# fite-controller-1-main.net
KiCad netlist of a schematic drawn in EAGLE
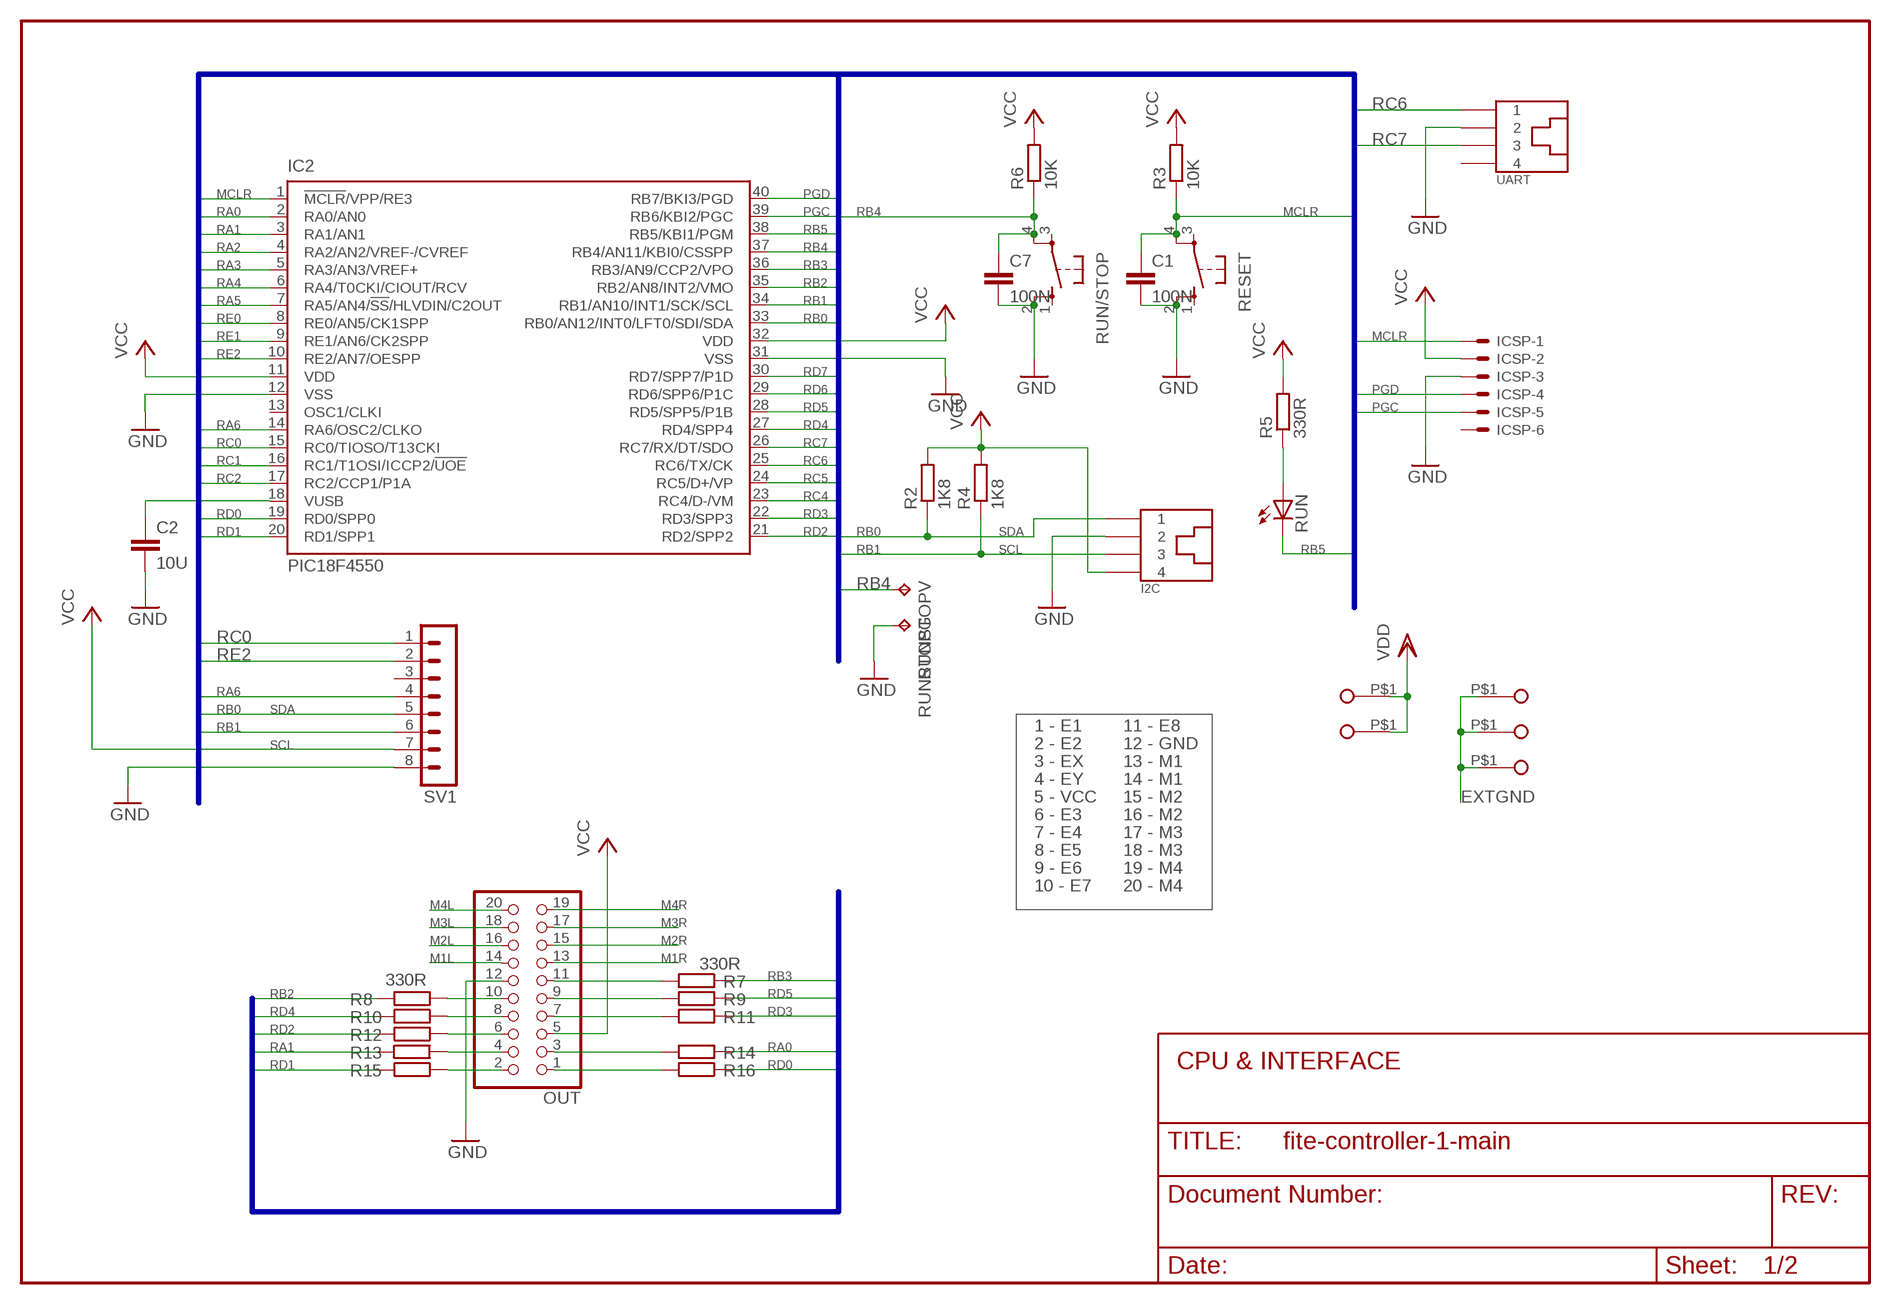
[diagram p0: schematic, sheet 1]
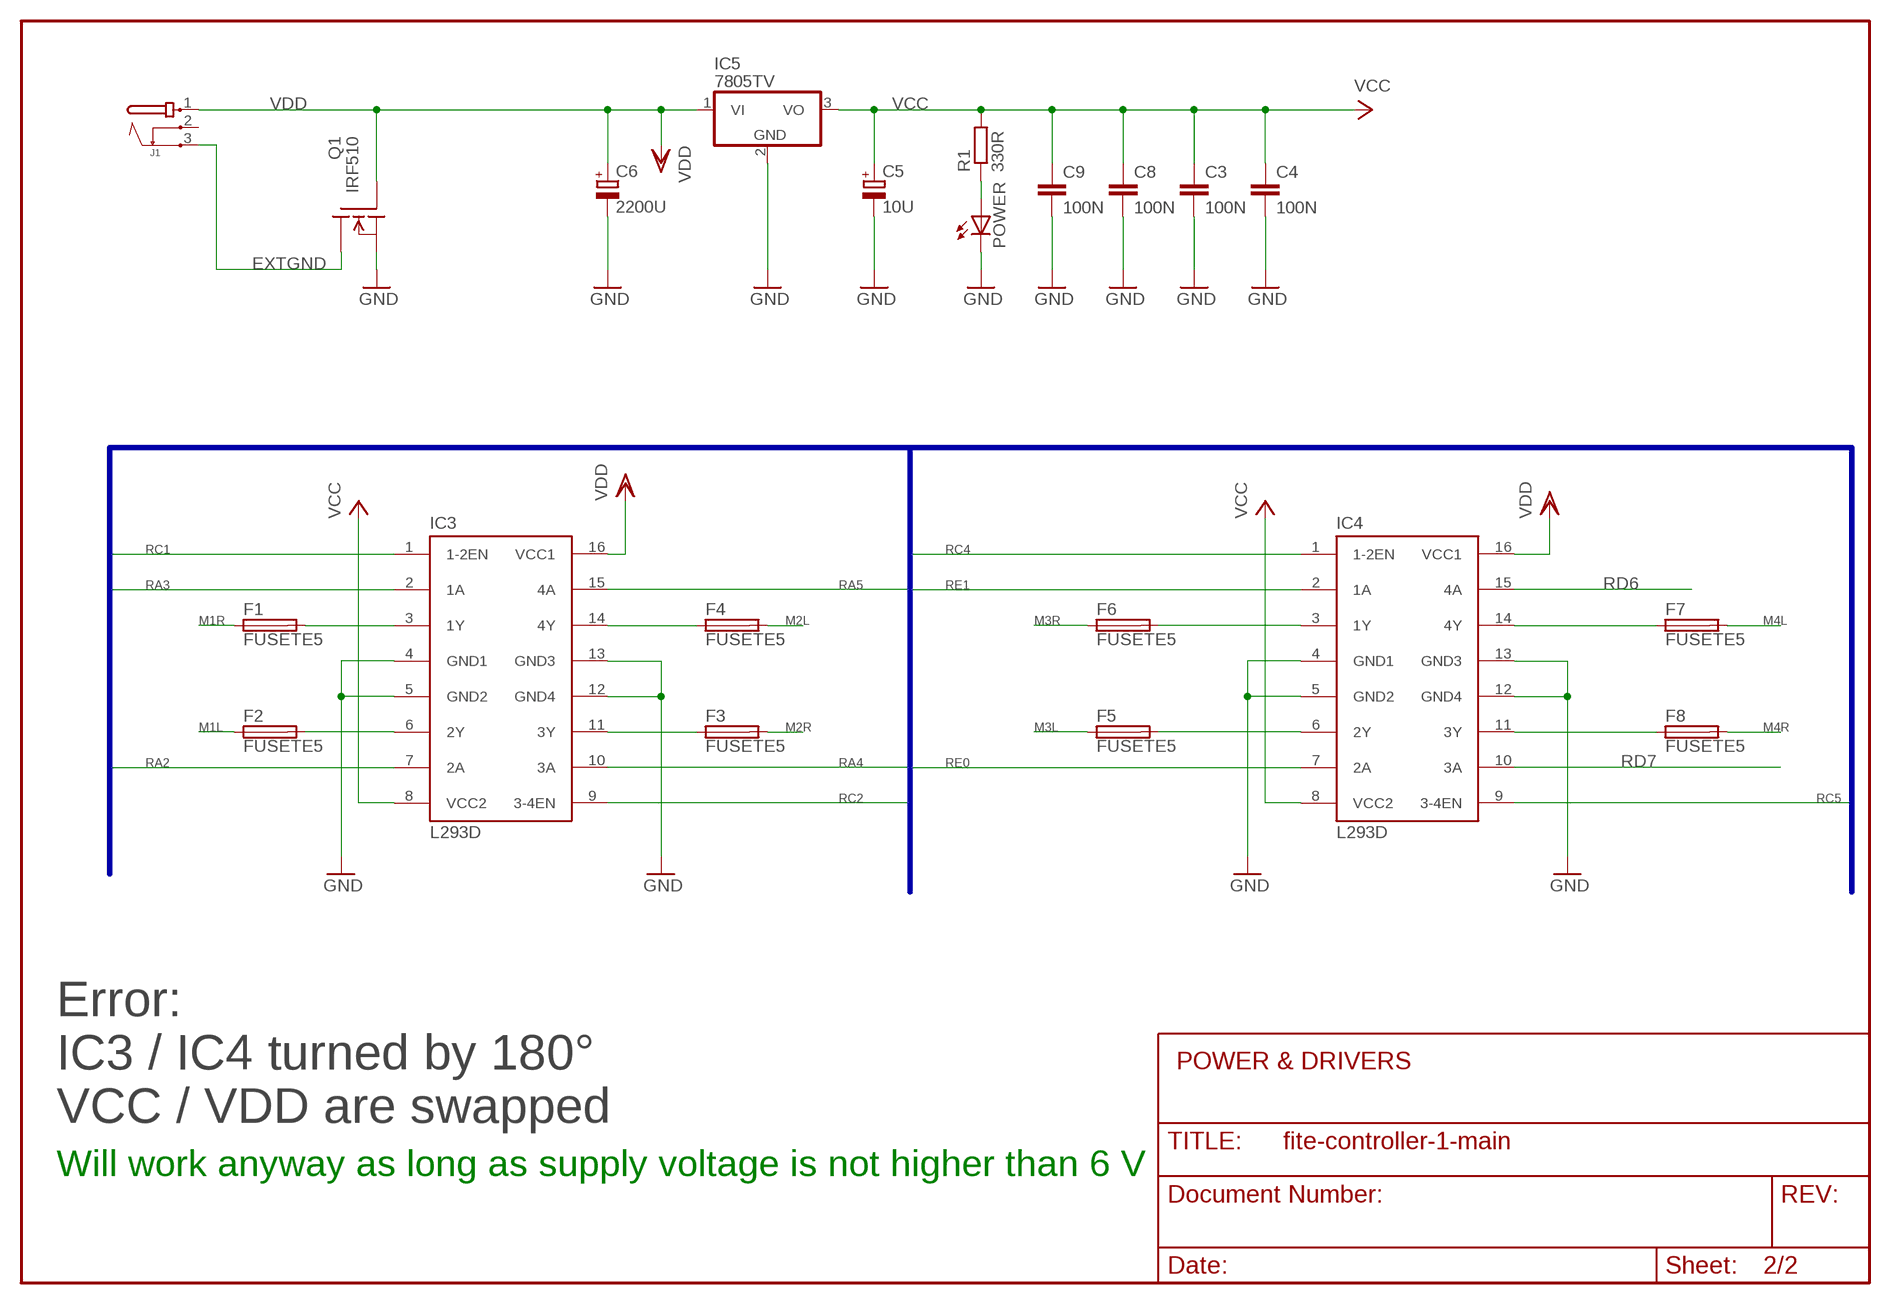
[diagram p1: schematic, sheet 2]

(export (version "E")
  (design (tool "Eeschema 10.0.6"))
  (components
    (comp (ref "C3")
      (value "100N")
      (footprint "eagle-import:C025-025X050")
      (libsource (lib "eagle-import") (part "C-EU025-025X050"))
    )
    (comp (ref "C4")
      (value "100N")
      (footprint "eagle-import:C025-025X050")
      (libsource (lib "eagle-import") (part "C-EU025-025X050"))
    )
    (comp (ref "C5")
      (value "10U")
      (footprint "eagle-import:E2-4")
      (libsource (lib "eagle-import") (part "CPOL-EUE2-4"))
    )
    (comp (ref "C6")
      (value "2200U")
      (footprint "eagle-import:E3,5-10")
      (libsource (lib "eagle-import") (part "CPOL-EUE3.5-10"))
    )
    (comp (ref "C8")
      (value "100N")
      (footprint "eagle-import:C025-025X050")
      (libsource (lib "eagle-import") (part "C-EU025-025X050"))
    )
    (comp (ref "C9")
      (value "100N")
      (footprint "eagle-import:C025-025X050")
      (libsource (lib "eagle-import") (part "C-EU025-025X050"))
    )
    (comp (ref "F1")
      (value "FUSETE5")
      (footprint "eagle-import:TE5")
      (libsource (lib "eagle-import") (part "FUSETE5"))
    )
    (comp (ref "F2")
      (value "FUSETE5")
      (footprint "eagle-import:TE5")
      (libsource (lib "eagle-import") (part "FUSETE5"))
    )
    (comp (ref "F3")
      (value "FUSETE5")
      (footprint "eagle-import:TE5")
      (libsource (lib "eagle-import") (part "FUSETE5"))
    )
    (comp (ref "F4")
      (value "FUSETE5")
      (footprint "eagle-import:TE5")
      (libsource (lib "eagle-import") (part "FUSETE5"))
    )
    (comp (ref "F5")
      (value "FUSETE5")
      (footprint "eagle-import:TE5")
      (libsource (lib "eagle-import") (part "FUSETE5"))
    )
    (comp (ref "F6")
      (value "FUSETE5")
      (footprint "eagle-import:TE5")
      (libsource (lib "eagle-import") (part "FUSETE5"))
    )
    (comp (ref "F7")
      (value "FUSETE5")
      (footprint "eagle-import:TE5")
      (libsource (lib "eagle-import") (part "FUSETE5"))
    )
    (comp (ref "F8")
      (value "FUSETE5")
      (footprint "eagle-import:TE5")
      (libsource (lib "eagle-import") (part "FUSETE5"))
    )
    (comp (ref "IC3")
      (value "L293D")
      (footprint "eagle-import:DIL16")
      (fields (field (name "MF") "Arrow Electronics") (field (name "MPN") "L293E"))
      (libsource (lib "eagle-import") (part "L293E"))
    )
    (comp (ref "IC4")
      (value "L293D")
      (footprint "eagle-import:DIL16")
      (fields (field (name "MF") "Arrow Electronics") (field (name "MPN") "L293E"))
      (libsource (lib "eagle-import") (part "L293E"))
    )
    (comp (ref "IC5")
      (value "7805TV")
      (footprint "eagle-import:TO220V")
      (libsource (lib "eagle-import") (part "78TV05"))
    )
    (comp (ref "J1")
      (value "JACK-PMS")
      (footprint "eagle-import:JACK-PMS")
      (libsource (lib "eagle-import") (part "JACK-PMS"))
    )
    (comp (ref "POWER")
      (value "LED3MM")
      (footprint "eagle-import:LED3MM")
      (libsource (lib "eagle-import") (part "LED3MM"))
    )
    (comp (ref "Q1")
      (value "IRF510")
      (footprint "eagle-import:TO220")
      (libsource (lib "eagle-import") (part "IRF510"))
    )
    (comp (ref "R1")
      (value "330R")
      (footprint "eagle-import:0207_10")
      (libsource (lib "eagle-import") (part "R-EU_0207/10"))
    )
    (comp (ref "C1")
      (value "100N")
      (footprint "eagle-import:C025-025X050")
      (libsource (lib "eagle-import") (part "C-EU025-025X050"))
    )
    (comp (ref "C2")
      (value "10U")
      (footprint "eagle-import:C025-025X050")
      (libsource (lib "eagle-import") (part "C-EU025-025X050"))
    )
    (comp (ref "C7")
      (value "100N")
      (footprint "eagle-import:C025-025X050")
      (libsource (lib "eagle-import") (part "C-EU025-025X050"))
    )
    (comp (ref "I2C")
      (value "PC_INTERNAL_AUDIO_4")
      (footprint "eagle-import:PC_INTERNAL_AUDIO_4")
      (libsource (lib "eagle-import") (part "PC_INTERNAL_AUDIO_4"))
    )
    (comp (ref "IC2")
      (value "PIC18F4550")
      (footprint "eagle-import:DIL40")
      (fields (field (name "MF") "MICROCHIP") (field (name "MPN") "PIC18F4550-I/P"))
      (libsource (lib "eagle-import") (part "PIC18F4_40550"))
    )
    (comp (ref "ICSP")
      (value "22-23-2061")
      (footprint "eagle-import:22-23-2061")
      (fields (field (name "MF") "MOLEX"))
      (libsource (lib "eagle-import") (part "22-23-2061"))
    )
    (comp (ref "OUT")
      (value "PINHD-2X10")
      (footprint "eagle-import:2X10")
      (libsource (lib "eagle-import") (part "PINHD-2X10"))
    )
    (comp (ref "R2")
      (value "1K8")
      (footprint "eagle-import:0207_10")
      (libsource (lib "eagle-import") (part "R-EU_0207/10"))
    )
    (comp (ref "R3")
      (value "10K")
      (footprint "eagle-import:0207_10")
      (libsource (lib "eagle-import") (part "R-EU_0207/10"))
    )
    (comp (ref "R4")
      (value "1K8")
      (footprint "eagle-import:0207_10")
      (libsource (lib "eagle-import") (part "R-EU_0207/10"))
    )
    (comp (ref "R5")
      (value "330R")
      (footprint "eagle-import:0207_10")
      (libsource (lib "eagle-import") (part "R-EU_0207/10"))
    )
    (comp (ref "R6")
      (value "10K")
      (footprint "eagle-import:0207_10")
      (libsource (lib "eagle-import") (part "R-EU_0207/10"))
    )
    (comp (ref "R7")
      (value "330R")
      (footprint "eagle-import:0207_10")
      (libsource (lib "eagle-import") (part "R-EU_0207/10"))
    )
    (comp (ref "R8")
      (value "330R")
      (footprint "eagle-import:0207_10")
      (libsource (lib "eagle-import") (part "R-EU_0207/10"))
    )
    (comp (ref "R9")
      (value "330R")
      (footprint "eagle-import:0207_10")
      (libsource (lib "eagle-import") (part "R-EU_0207/10"))
    )
    (comp (ref "R10")
      (value "330R")
      (footprint "eagle-import:0207_10")
      (libsource (lib "eagle-import") (part "R-EU_0207/10"))
    )
    (comp (ref "R11")
      (value "330R")
      (footprint "eagle-import:0207_10")
      (libsource (lib "eagle-import") (part "R-EU_0207/10"))
    )
    (comp (ref "R12")
      (value "330R")
      (footprint "eagle-import:0207_10")
      (libsource (lib "eagle-import") (part "R-EU_0207/10"))
    )
    (comp (ref "R13")
      (value "330R")
      (footprint "eagle-import:0207_10")
      (libsource (lib "eagle-import") (part "R-EU_0207/10"))
    )
    (comp (ref "R14")
      (value "330R")
      (footprint "eagle-import:0207_10")
      (libsource (lib "eagle-import") (part "R-EU_0207/10"))
    )
    (comp (ref "R15")
      (value "330R")
      (footprint "eagle-import:0207_10")
      (libsource (lib "eagle-import") (part "R-EU_0207/10"))
    )
    (comp (ref "R16")
      (value "330R")
      (footprint "eagle-import:0207_10")
      (libsource (lib "eagle-import") (part "R-EU_0207/10"))
    )
    (comp (ref "RESET")
      (value "10XX")
      (footprint "eagle-import:B3F-10XX")
      (libsource (lib "eagle-import") (part "10XX"))
    )
    (comp (ref "RUN")
      (value "LED3MM")
      (footprint "eagle-import:LED3MM")
      (libsource (lib "eagle-import") (part "LED3MM"))
    )
    (comp (ref "RUN/STOP")
      (value "10XX")
      (footprint "eagle-import:B3F-10XX")
      (libsource (lib "eagle-import") (part "10XX"))
    )
    (comp (ref "RUNSTOPG")
      (value "TPPAD1-13Y")
      (footprint "eagle-import:P1-13Y")
      (libsource (lib "eagle-import") (part "TPPAD1-13Y"))
    )
    (comp (ref "RUNSTOPV")
      (value "TPPAD1-13Y")
      (footprint "eagle-import:P1-13Y")
      (libsource (lib "eagle-import") (part "TPPAD1-13Y"))
    )
    (comp (ref "SV1")
      (value "MA08-1")
      (footprint "eagle-import:MA08-1")
      (libsource (lib "eagle-import") (part "MA08-1"))
    )
    (comp (ref "UART")
      (value "PC_INTERNAL_AUDIO_4")
      (footprint "eagle-import:PC_INTERNAL_AUDIO_4")
      (libsource (lib "eagle-import") (part "PC_INTERNAL_AUDIO_4"))
    )
    (comp (ref "VBB_GND_1")
      (value "FITE_HUELSE")
      (footprint "eagle-import:HUELSE_3.2MM")
      (libsource (lib "eagle-import") (part "FITE_HUELSE"))
    )
    (comp (ref "VDD_1")
      (value "FITE_HUELSE")
      (footprint "eagle-import:HUELSE_3.2MM")
      (libsource (lib "eagle-import") (part "FITE_HUELSE"))
    )
    (comp (ref "VDD_2")
      (value "FITE_HUELSE")
      (footprint "eagle-import:HUELSE_3.2MM")
      (libsource (lib "eagle-import") (part "FITE_HUELSE"))
    )
    (comp (ref "VDD_GND")
      (value "FITE_HUELSE")
      (footprint "eagle-import:HUELSE_3.2MM")
      (libsource (lib "eagle-import") (part "FITE_HUELSE"))
    )
    (comp (ref "VDD_GND_2")
      (value "FITE_HUELSE")
      (footprint "eagle-import:HUELSE_3.2MM")
      (libsource (lib "eagle-import") (part "FITE_HUELSE"))
    )
  )
  (nets
    (net (code "2") (name "EXTGND") (class "Default")
      (node (ref "J1") (pin "3") (pinfunction "3_3") (pintype "passive"))
      (node (ref "Q1") (pin "2") (pinfunction "D_2") (pintype "passive"))
      (node (ref "VBB_GND_1") (pin "P$1") (pinfunction "P$1_P$1") (pintype "bidirectional"))
      (node (ref "VDD_GND") (pin "P$1") (pinfunction "P$1_P$1") (pintype "bidirectional"))
      (node (ref "VDD_GND_2") (pin "P$1") (pinfunction "P$1_P$1") (pintype "bidirectional"))
    )
    (net (code "3") (name "GND") (class "Default")
      (node (ref "C1") (pin "2") (pinfunction "2_2") (pintype "passive"))
      (node (ref "C2") (pin "2") (pinfunction "2_2") (pintype "passive"))
      (node (ref "C3") (pin "2") (pinfunction "2_2") (pintype "passive"))
      (node (ref "C4") (pin "2") (pinfunction "2_2") (pintype "passive"))
      (node (ref "C5") (pin "-") (pinfunction "-_-") (pintype "passive"))
      (node (ref "C6") (pin "-") (pinfunction "-_-") (pintype "passive"))
      (node (ref "C7") (pin "2") (pinfunction "2_2") (pintype "passive"))
      (node (ref "C8") (pin "2") (pinfunction "2_2") (pintype "passive"))
      (node (ref "C9") (pin "2") (pinfunction "2_2") (pintype "passive"))
      (node (ref "I2C") (pin "P$2") (pinfunction "2_P$2") (pintype "bidirectional"))
      (node (ref "IC2") (pin "12") (pinfunction "VSS_12") (pintype "power_in"))
      (node (ref "IC2") (pin "31") (pinfunction "VSS_31") (pintype "power_in"))
      (node (ref "IC3") (pin "12") (pinfunction "GND4_12") (pintype "power_in"))
      (node (ref "IC3") (pin "13") (pinfunction "GND3_13") (pintype "power_in"))
      (node (ref "IC3") (pin "4") (pinfunction "GND1_4") (pintype "power_in"))
      (node (ref "IC3") (pin "5") (pinfunction "GND2_5") (pintype "power_in"))
      (node (ref "IC4") (pin "12") (pinfunction "GND4_12") (pintype "power_in"))
      (node (ref "IC4") (pin "13") (pinfunction "GND3_13") (pintype "power_in"))
      (node (ref "IC4") (pin "4") (pinfunction "GND1_4") (pintype "power_in"))
      (node (ref "IC4") (pin "5") (pinfunction "GND2_5") (pintype "power_in"))
      (node (ref "IC5") (pin "2") (pinfunction "GND_2") (pintype "passive"))
      (node (ref "ICSP") (pin "3") (pinfunction "S_3") (pintype "passive"))
      (node (ref "OUT") (pin "12") (pinfunction "12_12") (pintype "passive"))
      (node (ref "POWER") (pin "K") (pinfunction "C_K") (pintype "passive"))
      (node (ref "Q1") (pin "3") (pinfunction "S_3") (pintype "passive"))
      (node (ref "RESET") (pin "2") (pinfunction "2_2") (pintype "passive"))
      (node (ref "RUN/STOP") (pin "2") (pinfunction "2_2") (pintype "passive"))
      (node (ref "RUNSTOPG") (pin "TP") (pinfunction "TP_TP") (pintype "input"))
      (node (ref "SV1") (pin "8") (pinfunction "8_8") (pintype "passive"))
      (node (ref "UART") (pin "P$2") (pinfunction "2_P$2") (pintype "bidirectional"))
    )
    (net (code "4") (name "M1L") (class "Default")
      (node (ref "F2") (pin "1") (pinfunction "1_1") (pintype "passive"))
      (node (ref "OUT") (pin "14") (pinfunction "14_14") (pintype "passive"))
    )
    (net (code "5") (name "M1R") (class "Default")
      (node (ref "F1") (pin "1") (pinfunction "1_1") (pintype "passive"))
      (node (ref "OUT") (pin "13") (pinfunction "13_13") (pintype "passive"))
    )
    (net (code "6") (name "M2L") (class "Default")
      (node (ref "F4") (pin "2") (pinfunction "2_2") (pintype "passive"))
      (node (ref "OUT") (pin "16") (pinfunction "16_16") (pintype "passive"))
    )
    (net (code "7") (name "M2R") (class "Default")
      (node (ref "F3") (pin "2") (pinfunction "2_2") (pintype "passive"))
      (node (ref "OUT") (pin "15") (pinfunction "15_15") (pintype "passive"))
    )
    (net (code "8") (name "M3L") (class "Default")
      (node (ref "F5") (pin "1") (pinfunction "1_1") (pintype "passive"))
      (node (ref "OUT") (pin "18") (pinfunction "18_18") (pintype "passive"))
    )
    (net (code "9") (name "M3R") (class "Default")
      (node (ref "F6") (pin "1") (pinfunction "1_1") (pintype "passive"))
      (node (ref "OUT") (pin "17") (pinfunction "17_17") (pintype "passive"))
    )
    (net (code "10") (name "M4L") (class "Default")
      (node (ref "F7") (pin "2") (pinfunction "2_2") (pintype "passive"))
      (node (ref "OUT") (pin "20") (pinfunction "20_20") (pintype "passive"))
    )
    (net (code "11") (name "M4R") (class "Default")
      (node (ref "F8") (pin "2") (pinfunction "2_2") (pintype "passive"))
      (node (ref "OUT") (pin "19") (pinfunction "19_19") (pintype "passive"))
    )
    (net (code "12") (name "MCLR") (class "Default")
      (node (ref "C1") (pin "1") (pinfunction "1_1") (pintype "passive"))
      (node (ref "IC2") (pin "1") (pinfunction "~{MCLR}/VPP/RE3_1") (pintype "input"))
      (node (ref "ICSP") (pin "1") (pinfunction "S_1") (pintype "passive"))
      (node (ref "R3") (pin "1") (pinfunction "1_1") (pintype "passive"))
      (node (ref "RESET") (pin "4") (pinfunction "4_4") (pintype "passive"))
    )
    (net (code "13") (name "Net-(IC2-VUSB)") (class "Default")
      (node (ref "C2") (pin "1") (pinfunction "1_1") (pintype "passive"))
      (node (ref "IC2") (pin "18") (pinfunction "VUSB_18") (pintype "bidirectional"))
    )
    (net (code "14") (name "Net-(IC3-1Y)") (class "Default")
      (node (ref "F1") (pin "2") (pinfunction "2_2") (pintype "passive"))
      (node (ref "IC3") (pin "3") (pinfunction "1Y_3") (pintype "output"))
    )
    (net (code "15") (name "Net-(IC3-2Y)") (class "Default")
      (node (ref "F2") (pin "2") (pinfunction "2_2") (pintype "passive"))
      (node (ref "IC3") (pin "6") (pinfunction "2Y_6") (pintype "output"))
    )
    (net (code "16") (name "Net-(IC3-3Y)") (class "Default")
      (node (ref "F3") (pin "1") (pinfunction "1_1") (pintype "passive"))
      (node (ref "IC3") (pin "11") (pinfunction "3Y_11") (pintype "output"))
    )
    (net (code "17") (name "Net-(IC3-4Y)") (class "Default")
      (node (ref "F4") (pin "1") (pinfunction "1_1") (pintype "passive"))
      (node (ref "IC3") (pin "14") (pinfunction "4Y_14") (pintype "output"))
    )
    (net (code "18") (name "Net-(IC4-1Y)") (class "Default")
      (node (ref "F6") (pin "2") (pinfunction "2_2") (pintype "passive"))
      (node (ref "IC4") (pin "3") (pinfunction "1Y_3") (pintype "output"))
    )
    (net (code "19") (name "Net-(IC4-2Y)") (class "Default")
      (node (ref "F5") (pin "2") (pinfunction "2_2") (pintype "passive"))
      (node (ref "IC4") (pin "6") (pinfunction "2Y_6") (pintype "output"))
    )
    (net (code "20") (name "Net-(IC4-3Y)") (class "Default")
      (node (ref "F8") (pin "1") (pinfunction "1_1") (pintype "passive"))
      (node (ref "IC4") (pin "11") (pinfunction "3Y_11") (pintype "output"))
    )
    (net (code "21") (name "Net-(IC4-4Y)") (class "Default")
      (node (ref "F7") (pin "1") (pinfunction "1_1") (pintype "passive"))
      (node (ref "IC4") (pin "14") (pinfunction "4Y_14") (pintype "output"))
    )
    (net (code "22") (name "Net-(OUT-Pad1)") (class "Default")
      (node (ref "OUT") (pin "1") (pinfunction "1_1") (pintype "passive"))
      (node (ref "R16") (pin "2") (pinfunction "2_2") (pintype "passive"))
    )
    (net (code "23") (name "Net-(OUT-Pad2)") (class "Default")
      (node (ref "OUT") (pin "2") (pinfunction "2_2") (pintype "passive"))
      (node (ref "R15") (pin "1") (pinfunction "1_1") (pintype "passive"))
    )
    (net (code "24") (name "Net-(OUT-Pad3)") (class "Default")
      (node (ref "OUT") (pin "3") (pinfunction "3_3") (pintype "passive"))
      (node (ref "R14") (pin "2") (pinfunction "2_2") (pintype "passive"))
    )
    (net (code "25") (name "Net-(OUT-Pad4)") (class "Default")
      (node (ref "OUT") (pin "4") (pinfunction "4_4") (pintype "passive"))
      (node (ref "R13") (pin "2") (pinfunction "2_2") (pintype "passive"))
    )
    (net (code "26") (name "Net-(OUT-Pad6)") (class "Default")
      (node (ref "OUT") (pin "6") (pinfunction "6_6") (pintype "passive"))
      (node (ref "R12") (pin "1") (pinfunction "1_1") (pintype "passive"))
    )
    (net (code "27") (name "Net-(OUT-Pad7)") (class "Default")
      (node (ref "OUT") (pin "7") (pinfunction "7_7") (pintype "passive"))
      (node (ref "R11") (pin "2") (pinfunction "2_2") (pintype "passive"))
    )
    (net (code "28") (name "Net-(OUT-Pad8)") (class "Default")
      (node (ref "OUT") (pin "8") (pinfunction "8_8") (pintype "passive"))
      (node (ref "R10") (pin "1") (pinfunction "1_1") (pintype "passive"))
    )
    (net (code "29") (name "Net-(OUT-Pad9)") (class "Default")
      (node (ref "OUT") (pin "9") (pinfunction "9_9") (pintype "passive"))
      (node (ref "R9") (pin "2") (pinfunction "2_2") (pintype "passive"))
    )
    (net (code "30") (name "Net-(OUT-Pad10)") (class "Default")
      (node (ref "OUT") (pin "10") (pinfunction "10_10") (pintype "passive"))
      (node (ref "R8") (pin "1") (pinfunction "1_1") (pintype "passive"))
    )
    (net (code "31") (name "Net-(OUT-Pad11)") (class "Default")
      (node (ref "OUT") (pin "11") (pinfunction "11_11") (pintype "passive"))
      (node (ref "R7") (pin "2") (pinfunction "2_2") (pintype "passive"))
    )
    (net (code "32") (name "Net-(POWER-PadA)") (class "Default")
      (node (ref "POWER") (pin "A") (pinfunction "A_A") (pintype "passive"))
      (node (ref "R1") (pin "1") (pinfunction "1_1") (pintype "passive"))
    )
    (net (code "33") (name "Net-(R5-Pad1)") (class "Default")
      (node (ref "R5") (pin "1") (pinfunction "1_1") (pintype "passive"))
      (node (ref "RUN") (pin "A") (pinfunction "A_A") (pintype "passive"))
    )
    (net (code "34") (name "PGC") (class "Default")
      (node (ref "IC2") (pin "39") (pinfunction "RB6/KBI2/PGC_39") (pintype "bidirectional"))
      (node (ref "ICSP") (pin "5") (pinfunction "S_5") (pintype "passive"))
    )
    (net (code "35") (name "PGD") (class "Default")
      (node (ref "IC2") (pin "40") (pinfunction "RB7/BKI3/PGD_40") (pintype "bidirectional"))
      (node (ref "ICSP") (pin "4") (pinfunction "S_4") (pintype "passive"))
    )
    (net (code "36") (name "RA0") (class "Default")
      (node (ref "IC2") (pin "2") (pinfunction "RA0/AN0_2") (pintype "bidirectional"))
      (node (ref "R14") (pin "1") (pinfunction "1_1") (pintype "passive"))
    )
    (net (code "37") (name "RA1") (class "Default")
      (node (ref "IC2") (pin "3") (pinfunction "RA1/AN1_3") (pintype "bidirectional"))
      (node (ref "R13") (pin "1") (pinfunction "1_1") (pintype "passive"))
    )
    (net (code "38") (name "RA2") (class "Default")
      (node (ref "IC2") (pin "4") (pinfunction "RA2/AN2/VREF-/CVREF_4") (pintype "bidirectional"))
      (node (ref "IC3") (pin "7") (pinfunction "2A_7") (pintype "input"))
    )
    (net (code "39") (name "RA3") (class "Default")
      (node (ref "IC2") (pin "5") (pinfunction "RA3/AN3/VREF+_5") (pintype "bidirectional"))
      (node (ref "IC3") (pin "2") (pinfunction "1A_2") (pintype "input"))
    )
    (net (code "40") (name "RA4") (class "Default")
      (node (ref "IC2") (pin "6") (pinfunction "RA4/T0CKI/CIOUT/RCV_6") (pintype "bidirectional"))
      (node (ref "IC3") (pin "10") (pinfunction "3A_10") (pintype "input"))
    )
    (net (code "41") (name "RA5") (class "Default")
      (node (ref "IC2") (pin "7") (pinfunction "RA5/AN4/~{SS}/HLVDIN/C2OUT_7") (pintype "bidirectional"))
      (node (ref "IC3") (pin "15") (pinfunction "4A_15") (pintype "input"))
    )
    (net (code "42") (name "RA6") (class "Default")
      (node (ref "IC2") (pin "14") (pinfunction "RA6/OSC2/CLKO_14") (pintype "output"))
      (node (ref "SV1") (pin "4") (pinfunction "4_4") (pintype "passive"))
    )
    (net (code "43") (name "RB0") (class "Default")
      (node (ref "I2C") (pin "P$1") (pinfunction "1_P$1") (pintype "bidirectional"))
      (node (ref "IC2") (pin "33") (pinfunction "RB0/AN12/INT0/LFT0/SDI/SDA_33") (pintype "bidirectional"))
      (node (ref "R2") (pin "1") (pinfunction "1_1") (pintype "passive"))
      (node (ref "SV1") (pin "5") (pinfunction "5_5") (pintype "passive"))
    )
    (net (code "44") (name "RB1") (class "Default")
      (node (ref "I2C") (pin "P$3") (pinfunction "3_P$3") (pintype "bidirectional"))
      (node (ref "IC2") (pin "34") (pinfunction "RB1/AN10/INT1/SCK/SCL_34") (pintype "bidirectional"))
      (node (ref "R4") (pin "1") (pinfunction "1_1") (pintype "passive"))
      (node (ref "SV1") (pin "6") (pinfunction "6_6") (pintype "passive"))
    )
    (net (code "45") (name "RB2") (class "Default")
      (node (ref "IC2") (pin "35") (pinfunction "RB2/AN8/INT2/VMO_35") (pintype "bidirectional"))
      (node (ref "R8") (pin "2") (pinfunction "2_2") (pintype "passive"))
    )
    (net (code "46") (name "RB3") (class "Default")
      (node (ref "IC2") (pin "36") (pinfunction "RB3/AN9/CCP2/VPO_36") (pintype "bidirectional"))
      (node (ref "R7") (pin "1") (pinfunction "1_1") (pintype "passive"))
    )
    (net (code "47") (name "RB4") (class "Default")
      (node (ref "C7") (pin "1") (pinfunction "1_1") (pintype "passive"))
      (node (ref "IC2") (pin "37") (pinfunction "RB4/AN11/KBI0/CSSPP_37") (pintype "bidirectional"))
      (node (ref "R6") (pin "1") (pinfunction "1_1") (pintype "passive"))
      (node (ref "RUN/STOP") (pin "4") (pinfunction "4_4") (pintype "passive"))
      (node (ref "RUNSTOPV") (pin "TP") (pinfunction "TP_TP") (pintype "input"))
    )
    (net (code "48") (name "RB5") (class "Default")
      (node (ref "IC2") (pin "38") (pinfunction "RB5/KBI1/PGM_38") (pintype "bidirectional"))
      (node (ref "RUN") (pin "K") (pinfunction "C_K") (pintype "passive"))
    )
    (net (code "49") (name "RC0") (class "Default")
      (node (ref "IC2") (pin "15") (pinfunction "RC0/TIOSO/T13CKI_15") (pintype "bidirectional"))
      (node (ref "SV1") (pin "1") (pinfunction "1_1") (pintype "passive"))
    )
    (net (code "50") (name "RC1") (class "Default")
      (node (ref "IC2") (pin "16") (pinfunction "RC1/T1OSI/ICCP2/~{UOE}_16") (pintype "bidirectional"))
      (node (ref "IC3") (pin "1") (pinfunction "1-2EN_1") (pintype "input"))
    )
    (net (code "51") (name "RC2") (class "Default")
      (node (ref "IC2") (pin "17") (pinfunction "RC2/CCP1/P1A_17") (pintype "bidirectional"))
      (node (ref "IC3") (pin "9") (pinfunction "3-4EN_9") (pintype "input"))
    )
    (net (code "52") (name "RC4") (class "Default")
      (node (ref "IC2") (pin "23") (pinfunction "RC4/D-/VM_23") (pintype "bidirectional"))
      (node (ref "IC4") (pin "1") (pinfunction "1-2EN_1") (pintype "input"))
    )
    (net (code "53") (name "RC5") (class "Default")
      (node (ref "IC2") (pin "24") (pinfunction "RC5/D+/VP_24") (pintype "bidirectional"))
      (node (ref "IC4") (pin "9") (pinfunction "3-4EN_9") (pintype "input"))
    )
    (net (code "54") (name "RC6") (class "Default")
      (node (ref "IC2") (pin "25") (pinfunction "RC6/TX/CK_25") (pintype "bidirectional"))
      (node (ref "UART") (pin "P$1") (pinfunction "1_P$1") (pintype "bidirectional"))
    )
    (net (code "55") (name "RC7") (class "Default")
      (node (ref "IC2") (pin "26") (pinfunction "RC7/RX/DT/SDO_26") (pintype "bidirectional"))
      (node (ref "UART") (pin "P$3") (pinfunction "3_P$3") (pintype "bidirectional"))
    )
    (net (code "56") (name "RD0") (class "Default")
      (node (ref "IC2") (pin "19") (pinfunction "RD0/SPP0_19") (pintype "bidirectional"))
      (node (ref "R16") (pin "1") (pinfunction "1_1") (pintype "passive"))
    )
    (net (code "57") (name "RD1") (class "Default")
      (node (ref "IC2") (pin "20") (pinfunction "RD1/SPP1_20") (pintype "bidirectional"))
      (node (ref "R15") (pin "2") (pinfunction "2_2") (pintype "passive"))
    )
    (net (code "58") (name "RD2") (class "Default")
      (node (ref "IC2") (pin "21") (pinfunction "RD2/SPP2_21") (pintype "bidirectional"))
      (node (ref "R12") (pin "2") (pinfunction "2_2") (pintype "passive"))
    )
    (net (code "59") (name "RD3") (class "Default")
      (node (ref "IC2") (pin "22") (pinfunction "RD3/SPP3_22") (pintype "bidirectional"))
      (node (ref "R11") (pin "1") (pinfunction "1_1") (pintype "passive"))
    )
    (net (code "60") (name "RD4") (class "Default")
      (node (ref "IC2") (pin "27") (pinfunction "RD4/SPP4_27") (pintype "bidirectional"))
      (node (ref "R10") (pin "2") (pinfunction "2_2") (pintype "passive"))
    )
    (net (code "61") (name "RD5") (class "Default")
      (node (ref "IC2") (pin "28") (pinfunction "RD5/SPP5/P1B_28") (pintype "bidirectional"))
      (node (ref "R9") (pin "1") (pinfunction "1_1") (pintype "passive"))
    )
    (net (code "62") (name "RD6") (class "Default")
      (node (ref "IC2") (pin "29") (pinfunction "RD6/SPP6/P1C_29") (pintype "bidirectional"))
      (node (ref "IC4") (pin "15") (pinfunction "4A_15") (pintype "input"))
    )
    (net (code "63") (name "RD7") (class "Default")
      (node (ref "IC2") (pin "30") (pinfunction "RD7/SPP7/P1D_30") (pintype "bidirectional"))
      (node (ref "IC4") (pin "10") (pinfunction "3A_10") (pintype "input"))
    )
    (net (code "64") (name "RE0") (class "Default")
      (node (ref "IC2") (pin "8") (pinfunction "RE0/AN5/CK1SPP_8") (pintype "bidirectional"))
      (node (ref "IC4") (pin "7") (pinfunction "2A_7") (pintype "input"))
    )
    (net (code "65") (name "RE1") (class "Default")
      (node (ref "IC2") (pin "9") (pinfunction "RE1/AN6/CK2SPP_9") (pintype "bidirectional"))
      (node (ref "IC4") (pin "2") (pinfunction "1A_2") (pintype "input"))
    )
    (net (code "66") (name "RE2") (class "Default")
      (node (ref "IC2") (pin "10") (pinfunction "RE2/AN7/OESPP_10") (pintype "bidirectional"))
      (node (ref "SV1") (pin "2") (pinfunction "2_2") (pintype "passive"))
    )
    (net (code "67") (name "VCC") (class "Default")
      (node (ref "C3") (pin "1") (pinfunction "1_1") (pintype "passive"))
      (node (ref "C4") (pin "1") (pinfunction "1_1") (pintype "passive"))
      (node (ref "C5") (pin "+") (pinfunction "+_+") (pintype "passive"))
      (node (ref "C8") (pin "1") (pinfunction "1_1") (pintype "passive"))
      (node (ref "C9") (pin "1") (pinfunction "1_1") (pintype "passive"))
      (node (ref "I2C") (pin "P$4") (pinfunction "4_P$4") (pintype "bidirectional"))
      (node (ref "IC2") (pin "11") (pinfunction "VDD_11") (pintype "power_in"))
      (node (ref "IC2") (pin "32") (pinfunction "VDD_32") (pintype "power_in"))
      (node (ref "IC3") (pin "8") (pinfunction "VCC2_8") (pintype "power_in"))
      (node (ref "IC4") (pin "8") (pinfunction "VCC2_8") (pintype "power_in"))
      (node (ref "IC5") (pin "3") (pinfunction "VO_3") (pintype "passive"))
      (node (ref "ICSP") (pin "2") (pinfunction "S_2") (pintype "passive"))
      (node (ref "OUT") (pin "5") (pinfunction "5_5") (pintype "passive"))
      (node (ref "R1") (pin "2") (pinfunction "2_2") (pintype "passive"))
      (node (ref "R2") (pin "2") (pinfunction "2_2") (pintype "passive"))
      (node (ref "R3") (pin "2") (pinfunction "2_2") (pintype "passive"))
      (node (ref "R4") (pin "2") (pinfunction "2_2") (pintype "passive"))
      (node (ref "R5") (pin "2") (pinfunction "2_2") (pintype "passive"))
      (node (ref "R6") (pin "2") (pinfunction "2_2") (pintype "passive"))
      (node (ref "SV1") (pin "7") (pinfunction "7_7") (pintype "passive"))
    )
    (net (code "68") (name "VDD") (class "Default")
      (node (ref "C6") (pin "+") (pinfunction "+_+") (pintype "passive"))
      (node (ref "IC3") (pin "16") (pinfunction "VCC1_16") (pintype "power_in"))
      (node (ref "IC4") (pin "16") (pinfunction "VCC1_16") (pintype "power_in"))
      (node (ref "IC5") (pin "1") (pinfunction "VI_1") (pintype "input"))
      (node (ref "J1") (pin "1") (pinfunction "1_1") (pintype "passive"))
      (node (ref "Q1") (pin "1") (pinfunction "G_1") (pintype "passive"))
      (node (ref "VDD_1") (pin "P$1") (pinfunction "P$1_P$1") (pintype "bidirectional"))
      (node (ref "VDD_2") (pin "P$1") (pinfunction "P$1_P$1") (pintype "bidirectional"))
    )
    (net (code "69") (name "unconnected-(IC2-OSC1{slash}CLKI-Pad13)") (class "Default")
      (node (ref "IC2") (pin "13") (pinfunction "OSC1/CLKI_13") (pintype "input"))
    )
    (net (code "70") (name "unconnected-(ICSPF-S-Pad6)") (class "Default")
      (node (ref "ICSP") (pin "6") (pinfunction "S_6") (pintype "passive"))
    )
    (net (code "71") (name "unconnected-(J1-Pad2)") (class "Default")
      (node (ref "J1") (pin "2") (pinfunction "2_2") (pintype "passive"))
    )
    (net (code "72") (name "unconnected-(RESET-Pad1)") (class "Default")
      (node (ref "RESET") (pin "1") (pinfunction "1_1") (pintype "passive"))
    )
    (net (code "73") (name "unconnected-(RESET-Pad3)") (class "Default")
      (node (ref "RESET") (pin "3") (pinfunction "3_3") (pintype "passive"))
    )
    (net (code "74") (name "unconnected-(RUN/STOP-Pad1)") (class "Default")
      (node (ref "RUN/STOP") (pin "1") (pinfunction "1_1") (pintype "passive"))
    )
    (net (code "75") (name "unconnected-(RUN/STOP-Pad3)") (class "Default")
      (node (ref "RUN/STOP") (pin "3") (pinfunction "3_3") (pintype "passive"))
    )
    (net (code "76") (name "unconnected-(SV1-Pad3)") (class "Default")
      (node (ref "SV1") (pin "3") (pinfunction "3_3") (pintype "passive"))
    )
    (net (code "77") (name "unconnected-(UART-4-PadP$4)") (class "Default")
      (node (ref "UART") (pin "P$4") (pinfunction "4_P$4") (pintype "bidirectional"))
    )
  )
)
